# elektrosluch_mini.net
KiCad netlist of a schematic drawn in EAGLE
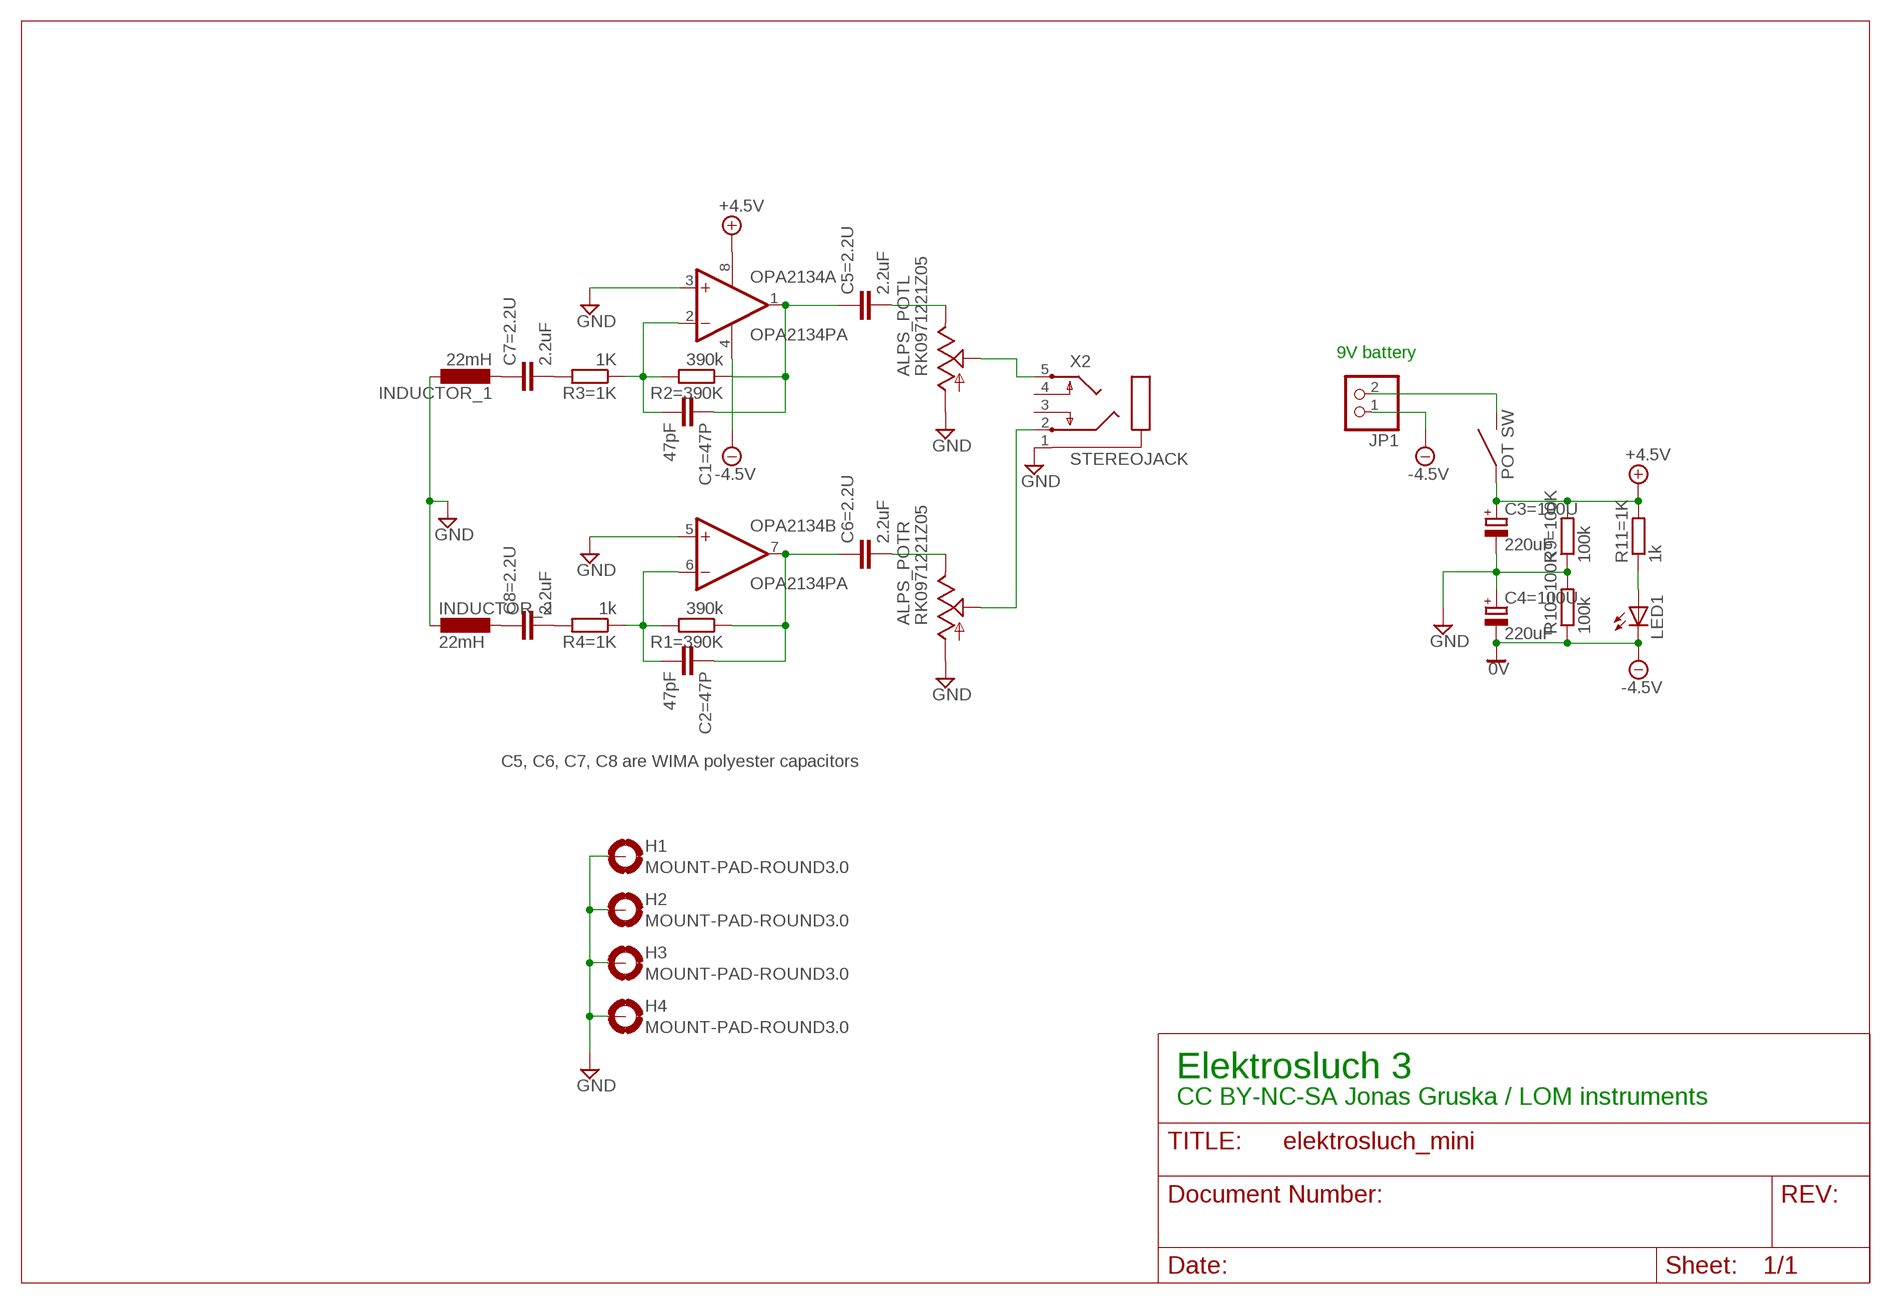
[diagram p0: schematic, sheet 1]

(export (version "E")
  (design (tool "Eeschema 10.0.6"))
  (components
    (comp (ref "ALPS_POT")
      (value "RK0971221Z05")
      (footprint "eagle-import:ALPS_RK0971221Z0X")
      (libsource (lib "eagle-import") (part "ALPS_RK0971221Z0N"))
    )
    (comp (ref "C1=47P")
      (value "47pF")
      (footprint "eagle-import:C050-024X044")
      (libsource (lib "eagle-import") (part "C-EU050-024X044"))
    )
    (comp (ref "C2=47P")
      (value "47pF")
      (footprint "eagle-import:C050-024X044")
      (libsource (lib "eagle-import") (part "C-EU050-024X044"))
    )
    (comp (ref "C3=100U")
      (value "220uF")
      (footprint "eagle-import:E2,5-5")
      (libsource (lib "eagle-import") (part "CPOL-EUE2.5-5"))
    )
    (comp (ref "C4=100U")
      (value "220uF")
      (footprint "eagle-import:E2,5-5")
      (libsource (lib "eagle-import") (part "CPOL-EUE2.5-5"))
    )
    (comp (ref "C5=2.2U")
      (value "2.2uF")
      (footprint "eagle-import:WIMA10UF")
      (libsource (lib "eagle-import") (part "WIMA10UF"))
    )
    (comp (ref "C6=2.2U")
      (value "2.2uF")
      (footprint "eagle-import:WIMA10UF")
      (libsource (lib "eagle-import") (part "WIMA10UF"))
    )
    (comp (ref "C7=2.2U")
      (value "2.2uF")
      (footprint "eagle-import:WIMA10UF")
      (libsource (lib "eagle-import") (part "WIMA10UF"))
    )
    (comp (ref "C8=2.2U")
      (value "2.2uF")
      (footprint "eagle-import:WIMA10UF")
      (libsource (lib "eagle-import") (part "WIMA10UF"))
    )
    (comp (ref "H1")
      (value "MOUNT-PAD-ROUND3.0")
      (footprint "eagle-import:3,0-PAD")
      (libsource (lib "eagle-import") (part "MOUNT-PAD-ROUND3.0"))
    )
    (comp (ref "H2")
      (value "MOUNT-PAD-ROUND3.0")
      (footprint "eagle-import:3,0-PAD")
      (libsource (lib "eagle-import") (part "MOUNT-PAD-ROUND3.0"))
    )
    (comp (ref "H3")
      (value "MOUNT-PAD-ROUND3.0")
      (footprint "eagle-import:3,0-PAD")
      (libsource (lib "eagle-import") (part "MOUNT-PAD-ROUND3.0"))
    )
    (comp (ref "H4")
      (value "MOUNT-PAD-ROUND3.0")
      (footprint "eagle-import:3,0-PAD")
      (libsource (lib "eagle-import") (part "MOUNT-PAD-ROUND3.0"))
    )
    (comp (ref "INDUCTOR_1")
      (value "22mH")
      (footprint "eagle-import:COIL")
      (libsource (lib "eagle-import") (part "COIL"))
    )
    (comp (ref "INDUCTOR_2")
      (value "22mH")
      (footprint "eagle-import:COIL")
      (libsource (lib "eagle-import") (part "COIL"))
    )
    (comp (ref "JP1")
      (value "PINHD-1X2")
      (footprint "eagle-import:1X02")
      (libsource (lib "eagle-import") (part "PINHD-1X2"))
    )
    (comp (ref "LED1")
      (value "LED3MM")
      (footprint "eagle-import:LED3MM")
      (libsource (lib "eagle-import") (part "LED3MM"))
    )
    (comp (ref "OPA2134")
      (value "OPA2134PA")
      (footprint "eagle-import:DIL08")
      (libsource (lib "eagle-import") (part "OPA2PA134"))
    )
    (comp (ref "R1=390K")
      (value "390k")
      (footprint "eagle-import:0207_10")
      (libsource (lib "eagle-import") (part "R-EU_0207/10"))
    )
    (comp (ref "R2=390K")
      (value "390k")
      (footprint "eagle-import:0207_10")
      (libsource (lib "eagle-import") (part "R-EU_0207/10"))
    )
    (comp (ref "R3=1K")
      (value "1K")
      (footprint "eagle-import:0207_10")
      (libsource (lib "eagle-import") (part "R-EU_0207/10"))
    )
    (comp (ref "R4=1K")
      (value "1k")
      (footprint "eagle-import:0207_10")
      (libsource (lib "eagle-import") (part "R-EU_0207/10"))
    )
    (comp (ref "R9=100K")
      (value "100k")
      (footprint "eagle-import:0207_10")
      (libsource (lib "eagle-import") (part "R-EU_0207/10"))
    )
    (comp (ref "R10=100K")
      (value "100k")
      (footprint "eagle-import:0207_10")
      (libsource (lib "eagle-import") (part "R-EU_0207/10"))
    )
    (comp (ref "R11=1K")
      (value "1k")
      (footprint "eagle-import:0207_10")
      (libsource (lib "eagle-import") (part "R-EU_0207/10"))
    )
    (comp (ref "X2")
      (value "STEREOJACK")
      (footprint "eagle-import:STX3100")
      (libsource (lib "eagle-import") (part "STEREOJACK"))
    )
  )
  (nets
    (net (code "1") (name "+4.5V") (class "Default")
      (node (ref "ALPS_POT") (pin "S1") (pinfunction "S1_S1") (pintype "power_in"))
      (node (ref "C3=100U") (pin "+") (pinfunction "+_+") (pintype "passive"))
      (node (ref "OPA2134") (pin "8") (pinfunction "V+_8") (pintype "power_in"))
      (node (ref "R11=1K") (pin "2") (pinfunction "2_2") (pintype "passive"))
      (node (ref "R9=100K") (pin "2") (pinfunction "2_2") (pintype "passive"))
    )
    (net (code "2") (name "-4.5V") (class "Default")
      (node (ref "C4=100U") (pin "-") (pinfunction "-_-") (pintype "passive"))
      (node (ref "JP1") (pin "1") (pinfunction "1_1") (pintype "passive"))
      (node (ref "LED1") (pin "K") (pinfunction "C_K") (pintype "passive"))
      (node (ref "OPA2134") (pin "4") (pinfunction "V-_4") (pintype "power_in"))
      (node (ref "R10=100K") (pin "1") (pinfunction "1_1") (pintype "passive"))
    )
    (net (code "3") (name "GND") (class "Default")
      (node (ref "ALPS_POT") (pin "G1") (pinfunction "1_G1") (pintype "passive"))
      (node (ref "ALPS_POT") (pin "G2") (pinfunction "1_G2") (pintype "passive"))
      (node (ref "C3=100U") (pin "-") (pinfunction "-_-") (pintype "passive"))
      (node (ref "C4=100U") (pin "+") (pinfunction "+_+") (pintype "passive"))
      (node (ref "H1") (pin "B3,0") (pinfunction "MOUNT_B3,0") (pintype "passive"))
      (node (ref "H2") (pin "B3,0") (pinfunction "MOUNT_B3,0") (pintype "passive"))
      (node (ref "H3") (pin "B3,0") (pinfunction "MOUNT_B3,0") (pintype "passive"))
      (node (ref "H4") (pin "B3,0") (pinfunction "MOUNT_B3,0") (pintype "passive"))
      (node (ref "INDUCTOR_1") (pin "P$1") (pinfunction "1_P$1") (pintype "passive"))
      (node (ref "INDUCTOR_2") (pin "P$2") (pinfunction "2_P$2") (pintype "passive"))
      (node (ref "OPA2134") (pin "3") (pinfunction "+IN_3") (pintype "input"))
      (node (ref "OPA2134") (pin "5") (pinfunction "+IN_5") (pintype "input"))
      (node (ref "R10=100K") (pin "2") (pinfunction "2_2") (pintype "passive"))
      (node (ref "R9=100K") (pin "1") (pinfunction "1_1") (pintype "passive"))
      (node (ref "X2") (pin "1") (pinfunction "1_1") (pintype "passive"))
    )
    (net (code "4") (name "Net-(ALPS_POT-PadS2)") (class "Default")
      (node (ref "ALPS_POT") (pin "S2") (pinfunction "S2_S2") (pintype "power_in"))
      (node (ref "JP1") (pin "2") (pinfunction "2_2") (pintype "passive"))
    )
    (net (code "5") (name "Net-(ALPS_POTB-2)") (class "Default")
      (node (ref "ALPS_POT") (pin "O1") (pinfunction "2_O1") (pintype "passive"))
      (node (ref "X2") (pin "5") (pinfunction "5_5") (pintype "passive"))
    )
    (net (code "6") (name "Net-(ALPS_POTB-3)") (class "Default")
      (node (ref "ALPS_POT") (pin "I1") (pinfunction "3_I1") (pintype "passive"))
      (node (ref "C5=2.2U") (pin "P$2") (pinfunction "2_P$2") (pintype "passive"))
    )
    (net (code "7") (name "Net-(ALPS_POTC-2)") (class "Default")
      (node (ref "ALPS_POT") (pin "O2") (pinfunction "2_O2") (pintype "passive"))
      (node (ref "X2") (pin "2") (pinfunction "2_2") (pintype "passive"))
    )
    (net (code "8") (name "Net-(ALPS_POTC-3)") (class "Default")
      (node (ref "ALPS_POT") (pin "I2") (pinfunction "3_I2") (pintype "passive"))
      (node (ref "C6=2.2U") (pin "P$2") (pinfunction "2_P$2") (pintype "passive"))
    )
    (net (code "9") (name "Net-(C5=2.2U-1)") (class "Default")
      (node (ref "C1=47P") (pin "1") (pinfunction "1_1") (pintype "passive"))
      (node (ref "C5=2.2U") (pin "P$1") (pinfunction "1_P$1") (pintype "passive"))
      (node (ref "OPA2134") (pin "1") (pinfunction "OUT_1") (pintype "output"))
      (node (ref "R2=390K") (pin "1") (pinfunction "1_1") (pintype "passive"))
    )
    (net (code "10") (name "Net-(C6=2.2U-1)") (class "Default")
      (node (ref "C2=47P") (pin "1") (pinfunction "1_1") (pintype "passive"))
      (node (ref "C6=2.2U") (pin "P$1") (pinfunction "1_P$1") (pintype "passive"))
      (node (ref "OPA2134") (pin "7") (pinfunction "OUT_7") (pintype "output"))
      (node (ref "R1=390K") (pin "1") (pinfunction "1_1") (pintype "passive"))
    )
    (net (code "11") (name "Net-(C7=2.2U-1)") (class "Default")
      (node (ref "C7=2.2U") (pin "P$1") (pinfunction "1_P$1") (pintype "passive"))
      (node (ref "INDUCTOR_1") (pin "P$2") (pinfunction "2_P$2") (pintype "passive"))
    )
    (net (code "12") (name "Net-(C7=2.2U-2)") (class "Default")
      (node (ref "C7=2.2U") (pin "P$2") (pinfunction "2_P$2") (pintype "passive"))
      (node (ref "R3=1K") (pin "2") (pinfunction "2_2") (pintype "passive"))
    )
    (net (code "13") (name "Net-(C8=2.2U-1)") (class "Default")
      (node (ref "C8=2.2U") (pin "P$1") (pinfunction "1_P$1") (pintype "passive"))
      (node (ref "INDUCTOR_2") (pin "P$1") (pinfunction "1_P$1") (pintype "passive"))
    )
    (net (code "14") (name "Net-(C8=2.2U-2)") (class "Default")
      (node (ref "C8=2.2U") (pin "P$2") (pinfunction "2_P$2") (pintype "passive"))
      (node (ref "R4=1K") (pin "2") (pinfunction "2_2") (pintype "passive"))
    )
    (net (code "15") (name "Net-(LED1-PadA)") (class "Default")
      (node (ref "LED1") (pin "A") (pinfunction "A_A") (pintype "passive"))
      (node (ref "R11=1K") (pin "1") (pinfunction "1_1") (pintype "passive"))
    )
    (net (code "16") (name "Net-(OPA2134A--IN)") (class "Default")
      (node (ref "C1=47P") (pin "2") (pinfunction "2_2") (pintype "passive"))
      (node (ref "OPA2134") (pin "2") (pinfunction "-IN_2") (pintype "input"))
      (node (ref "R2=390K") (pin "2") (pinfunction "2_2") (pintype "passive"))
      (node (ref "R3=1K") (pin "1") (pinfunction "1_1") (pintype "passive"))
    )
    (net (code "17") (name "Net-(OPA2134B--IN)") (class "Default")
      (node (ref "C2=47P") (pin "2") (pinfunction "2_2") (pintype "passive"))
      (node (ref "OPA2134") (pin "6") (pinfunction "-IN_6") (pintype "input"))
      (node (ref "R1=390K") (pin "2") (pinfunction "2_2") (pintype "passive"))
      (node (ref "R4=1K") (pin "1") (pinfunction "1_1") (pintype "passive"))
    )
    (net (code "18") (name "unconnected-(X2-Pad3)") (class "Default")
      (node (ref "X2") (pin "3") (pinfunction "3_3") (pintype "passive"))
    )
    (net (code "19") (name "unconnected-(X2-Pad4)") (class "Default")
      (node (ref "X2") (pin "4") (pinfunction "4_4") (pintype "passive"))
    )
  )
)
